# light_key_control.net
KiCad netlist of a schematic drawn in Altium Designer
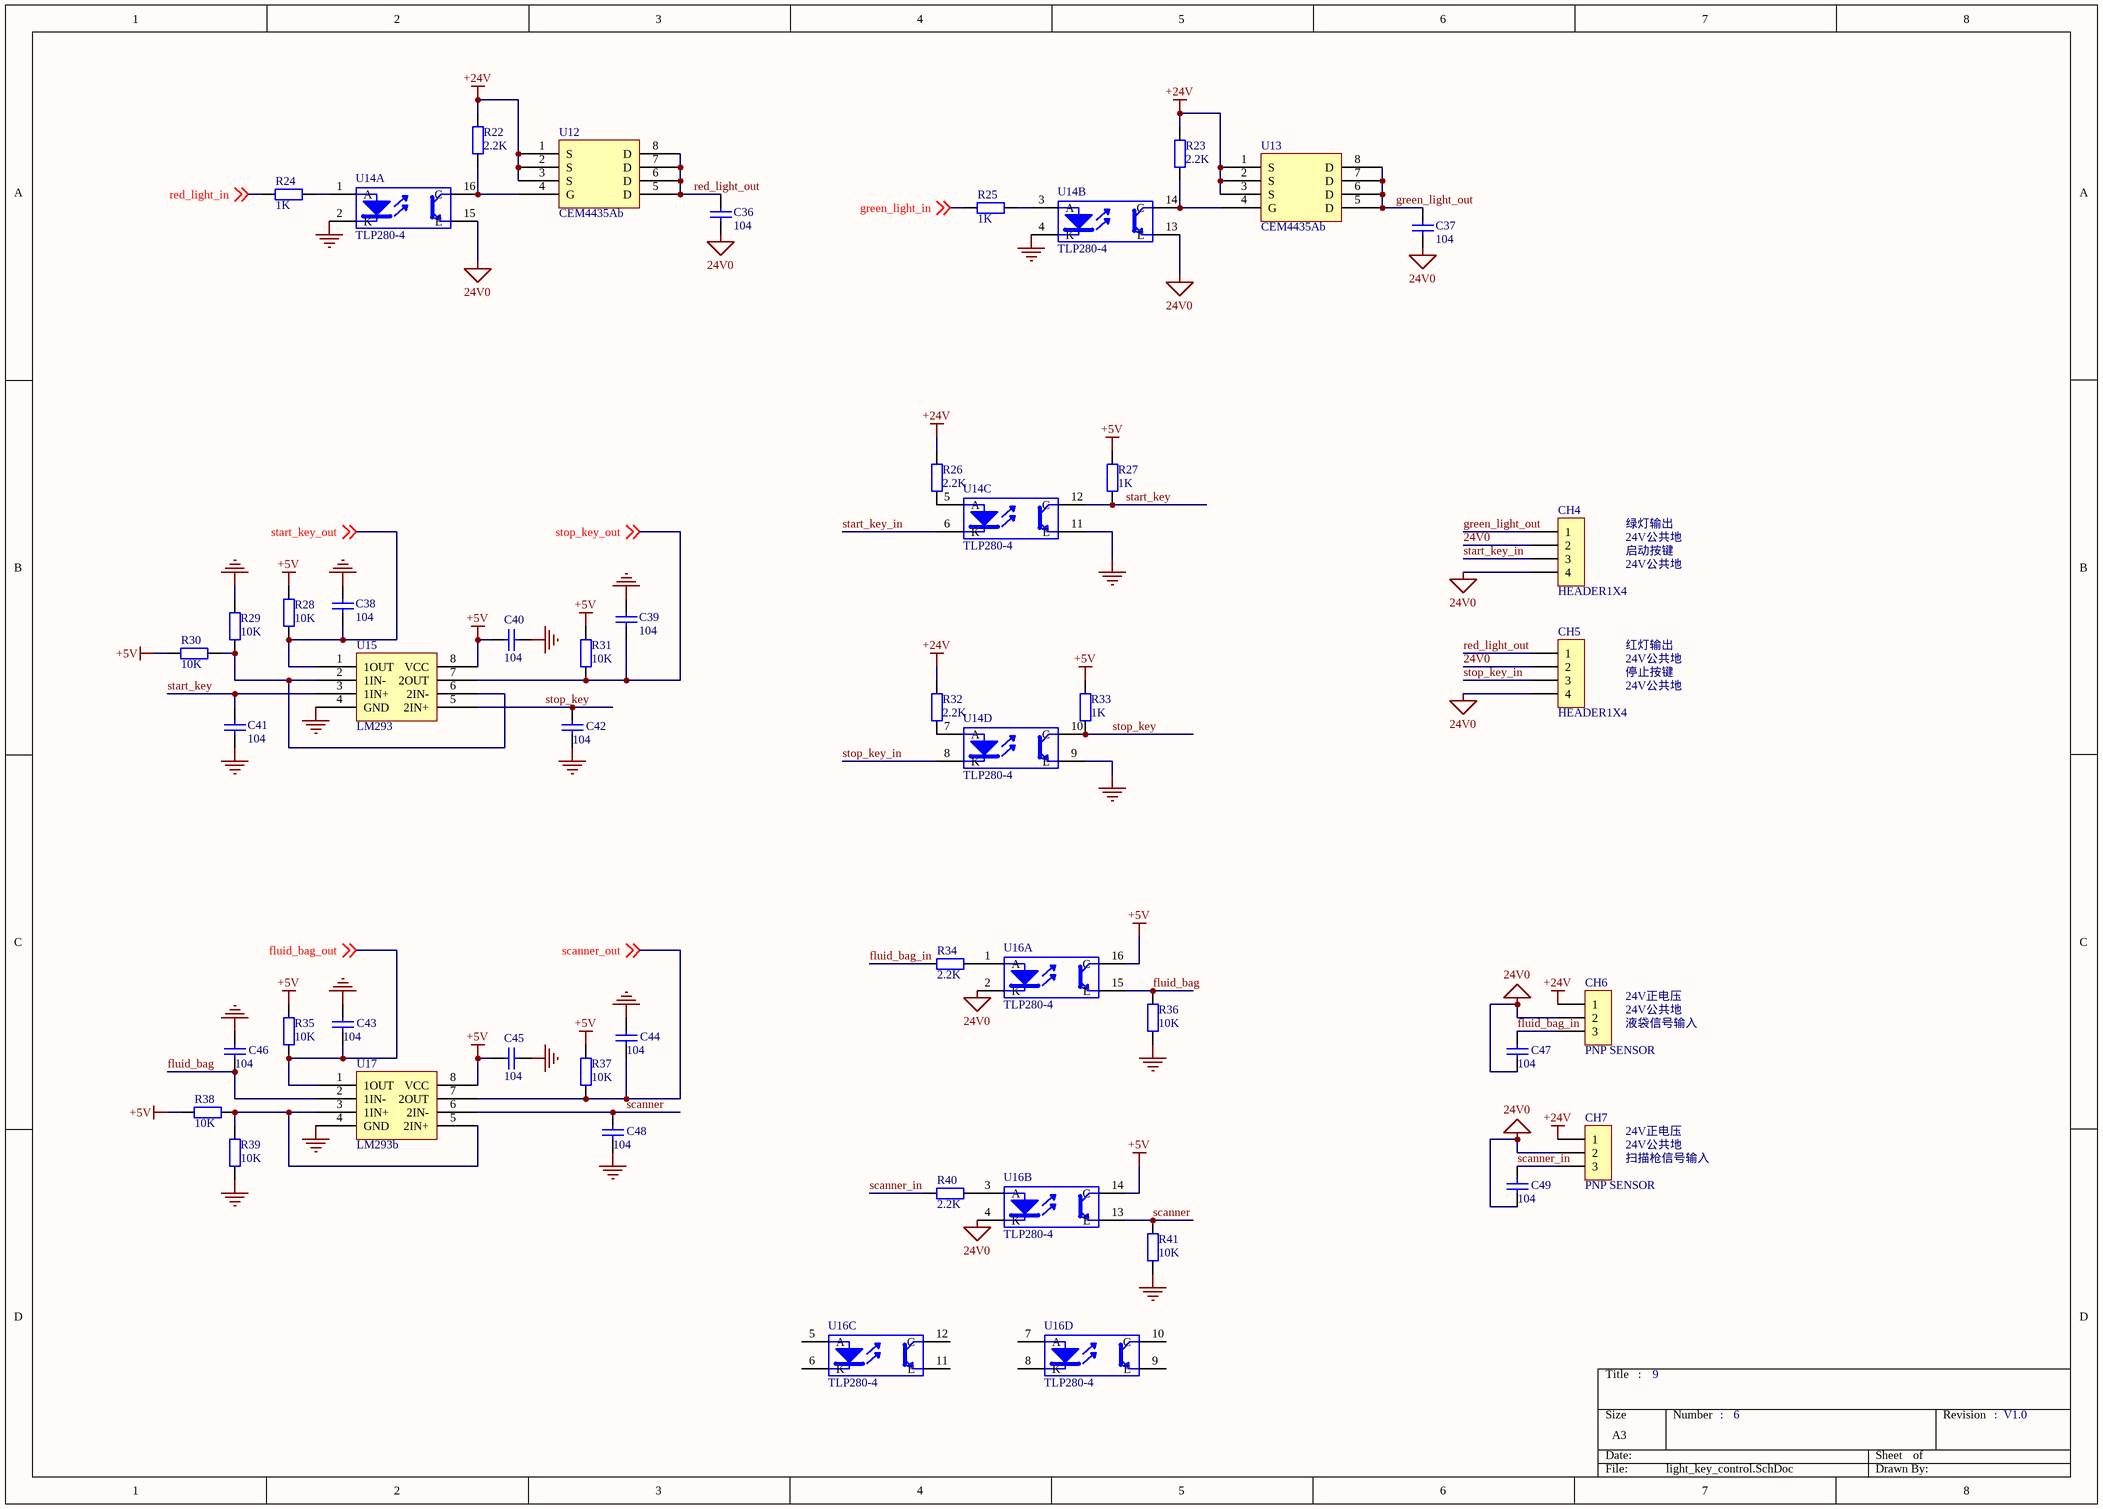
[diagram p0: light_key_control.SchDoc]

(export (version "E")
  (design (tool "Eeschema 10.0.6"))
  (components
    (comp (ref "C36")
      (value "104")
      (footprint "0805")
      (description "Capacitor")
      (fields (field (name "Comment") "Capb") (field (name "PUBLISHER") "Altium Limited"))
      (libsource (lib "Miscellaneous Devices") (part "Cap"))
    )
    (comp (ref "C37")
      (value "104")
      (footprint "0805")
      (description "Capacitor")
      (fields (field (name "Comment") "Capb") (field (name "PUBLISHER") "Altium Limited"))
      (libsource (lib "Miscellaneous Devices") (part "Cap"))
    )
    (comp (ref "C38")
      (value "104")
      (footprint "0805")
      (description "Capacitor")
      (fields (field (name "Comment") "Cap") (field (name "PUBLISHER") "Altium Limited"))
      (libsource (lib "Miscellaneous Devices") (part "Cap"))
    )
    (comp (ref "C39")
      (value "104")
      (footprint "0805")
      (description "Capacitor")
      (fields (field (name "Comment") "Cap") (field (name "PUBLISHER") "Altium Limited"))
      (libsource (lib "Miscellaneous Devices") (part "Cap"))
    )
    (comp (ref "C40")
      (value "104")
      (footprint "0805")
      (description "Capacitor")
      (fields (field (name "Comment") "Cap") (field (name "PUBLISHER") "Altium Limited"))
      (libsource (lib "Miscellaneous Devices") (part "Cap"))
    )
    (comp (ref "C41")
      (value "104")
      (footprint "0805")
      (description "Capacitor")
      (fields (field (name "Comment") "Cap") (field (name "PUBLISHER") "Altium Limited"))
      (libsource (lib "Miscellaneous Devices") (part "Cap"))
    )
    (comp (ref "C42")
      (value "104")
      (footprint "0805")
      (description "Capacitor")
      (fields (field (name "Comment") "Cap") (field (name "PUBLISHER") "Altium Limited"))
      (libsource (lib "Miscellaneous Devices") (part "Cap"))
    )
    (comp (ref "C43")
      (value "104")
      (footprint "0805")
      (description "Capacitor")
      (fields (field (name "Comment") "Capb") (field (name "PUBLISHER") "Altium Limited"))
      (libsource (lib "Miscellaneous Devices") (part "Cap"))
    )
    (comp (ref "C44")
      (value "104")
      (footprint "0805")
      (description "Capacitor")
      (fields (field (name "Comment") "Capb") (field (name "PUBLISHER") "Altium Limited"))
      (libsource (lib "Miscellaneous Devices") (part "Cap"))
    )
    (comp (ref "C45")
      (value "104")
      (footprint "0805")
      (description "Capacitor")
      (fields (field (name "Comment") "Cap") (field (name "PUBLISHER") "Altium Limited"))
      (libsource (lib "Miscellaneous Devices") (part "Cap"))
    )
    (comp (ref "C46")
      (value "104")
      (footprint "0805")
      (description "Capacitor")
      (fields (field (name "Comment") "Cap") (field (name "PUBLISHER") "Altium Limited"))
      (libsource (lib "Miscellaneous Devices") (part "Cap"))
    )
    (comp (ref "C47")
      (value "104")
      (footprint "0805")
      (description "Capacitor")
      (fields (field (name "Comment") "Capb") (field (name "PUBLISHER") "Altium Limited"))
      (libsource (lib "Miscellaneous Devices") (part "Cap"))
    )
    (comp (ref "C48")
      (value "104")
      (footprint "0805")
      (description "Capacitor")
      (fields (field (name "Comment") "Cap") (field (name "PUBLISHER") "Altium Limited"))
      (libsource (lib "Miscellaneous Devices") (part "Cap"))
    )
    (comp (ref "C49")
      (value "104")
      (footprint "0805")
      (description "Capacitor")
      (fields (field (name "Comment") "Capb") (field (name "PUBLISHER") "Altium Limited"))
      (libsource (lib "Miscellaneous Devices") (part "Cap"))
    )
    (comp (ref "CH4")
      (value "HEADER1X4")
      (footprint "CH3.96-4PIN")
      (libsource (lib "myIntegrated_Library1") (part "HEADER1X4"))
    )
    (comp (ref "CH5")
      (value "HEADER1X4")
      (footprint "CH3.96-4PIN")
      (libsource (lib "myIntegrated_Library1") (part "HEADER1X4"))
    )
    (comp (ref "CH6")
      (value "HEADER1X3")
      (footprint "CH3.96-3PIN")
      (fields (field (name "ALTIUM_UNNAMED_1") "PNP SENSOR"))
      (libsource (lib "myIntegrated_Library1") (part "HEADER1X3"))
    )
    (comp (ref "CH7")
      (value "HEADER1X3")
      (footprint "CH3.96-3PIN")
      (fields (field (name "ALTIUM_UNNAMED_1") "PNP SENSOR"))
      (libsource (lib "myIntegrated_Library1") (part "HEADER1X3"))
    )
    (comp (ref "R22")
      (value "2.2K")
      (footprint "0805")
      (description "Resistor")
      (fields (field (name "Comment") "Res2") (field (name "PUBLISHER") "Altium Limited"))
      (libsource (lib "") (part "Res2_3"))
    )
    (comp (ref "R23")
      (value "2.2K")
      (footprint "0805")
      (description "Resistor")
      (fields (field (name "Comment") "Res2") (field (name "PUBLISHER") "Altium Limited"))
      (libsource (lib "") (part "Res2_3"))
    )
    (comp (ref "R24")
      (value "1K")
      (footprint "0805")
      (description "Resistor")
      (fields (field (name "Comment") "Res2") (field (name "PUBLISHER") "Altium Limited"))
      (libsource (lib "Miscellaneous Devices") (part "Res2"))
    )
    (comp (ref "R25")
      (value "1K")
      (footprint "0805")
      (description "Resistor")
      (fields (field (name "Comment") "Res2") (field (name "PUBLISHER") "Altium Limited"))
      (libsource (lib "Miscellaneous Devices") (part "Res2"))
    )
    (comp (ref "R26")
      (value "2.2K")
      (footprint "0805")
      (description "Resistor")
      (fields (field (name "Comment") "Res2") (field (name "PUBLISHER") "Altium Limited"))
      (libsource (lib "") (part "Res2_1"))
    )
    (comp (ref "R27")
      (value "1K")
      (footprint "0805")
      (description "Resistor")
      (fields (field (name "Comment") "Res2") (field (name "PUBLISHER") "Altium Limited"))
      (libsource (lib "") (part "Res2_1"))
    )
    (comp (ref "R28")
      (value "10K")
      (footprint "0805")
      (description "Resistor")
      (fields (field (name "Comment") "Res2") (field (name "PUBLISHER") "Altium Limited"))
      (libsource (lib "") (part "Res2_1"))
    )
    (comp (ref "R29")
      (value "10K")
      (footprint "0805")
      (description "Resistor")
      (fields (field (name "Comment") "Res2") (field (name "PUBLISHER") "Altium Limited"))
      (libsource (lib "") (part "Res2_1"))
    )
    (comp (ref "R30")
      (value "10K")
      (footprint "0805")
      (description "Resistor")
      (fields (field (name "Comment") "Res2") (field (name "PUBLISHER") "Altium Limited"))
      (libsource (lib "") (part "Res2_2"))
    )
    (comp (ref "R31")
      (value "10K")
      (footprint "0805")
      (description "Resistor")
      (fields (field (name "Comment") "Res2") (field (name "PUBLISHER") "Altium Limited"))
      (libsource (lib "") (part "Res2_1"))
    )
    (comp (ref "R32")
      (value "2.2K")
      (footprint "0805")
      (description "Resistor")
      (fields (field (name "Comment") "Res2") (field (name "PUBLISHER") "Altium Limited"))
      (libsource (lib "") (part "Res2_1"))
    )
    (comp (ref "R33")
      (value "1K")
      (footprint "0805")
      (description "Resistor")
      (fields (field (name "Comment") "Res2") (field (name "PUBLISHER") "Altium Limited"))
      (libsource (lib "") (part "Res2_1"))
    )
    (comp (ref "R34")
      (value "2.2K")
      (footprint "0805")
      (description "Resistor")
      (fields (field (name "Comment") "Res2") (field (name "PUBLISHER") "Altium Limited"))
      (libsource (lib "") (part "Res2_2"))
    )
    (comp (ref "R35")
      (value "10K")
      (footprint "0805")
      (description "Resistor")
      (fields (field (name "Comment") "Res2b") (field (name "PUBLISHER") "Altium Limited"))
      (libsource (lib "") (part "Res2_1"))
    )
    (comp (ref "R36")
      (value "10K")
      (footprint "0805")
      (description "Resistor")
      (fields (field (name "Comment") "Res2") (field (name "PUBLISHER") "Altium Limited"))
      (libsource (lib "") (part "Res2_1"))
    )
    (comp (ref "R37")
      (value "10K")
      (footprint "0805")
      (description "Resistor")
      (fields (field (name "Comment") "Res2b") (field (name "PUBLISHER") "Altium Limited"))
      (libsource (lib "") (part "Res2_1"))
    )
    (comp (ref "R38")
      (value "10K")
      (footprint "0805")
      (description "Resistor")
      (fields (field (name "Comment") "Res2b") (field (name "PUBLISHER") "Altium Limited"))
      (libsource (lib "") (part "Res2_2"))
    )
    (comp (ref "R39")
      (value "10K")
      (footprint "0805")
      (description "Resistor")
      (fields (field (name "Comment") "Res2b") (field (name "PUBLISHER") "Altium Limited"))
      (libsource (lib "") (part "Res2_1"))
    )
    (comp (ref "R40")
      (value "2.2K")
      (footprint "0805")
      (description "Resistor")
      (fields (field (name "Comment") "Res2") (field (name "PUBLISHER") "Altium Limited"))
      (libsource (lib "") (part "Res2_2"))
    )
    (comp (ref "R41")
      (value "10K")
      (footprint "0805")
      (description "Resistor")
      (fields (field (name "Comment") "Res2") (field (name "PUBLISHER") "Altium Limited"))
      (libsource (lib "") (part "Res2_1"))
    )
    (comp (ref "U12")
      (value "CEM4435Ab")
      (footprint "SOP8-OP27")
      (libsource (lib "myIntegrated_Library1") (part "CEM4435A"))
    )
    (comp (ref "U13")
      (value "CEM4435Ab")
      (footprint "SOP8-OP27")
      (libsource (lib "myIntegrated_Library1") (part "CEM4435A"))
    )
    (comp (ref "U14") (value "TLP280-4") (footprint "SO16") (libsource (lib "WH V20") (part "TLP521-4")))
    (comp (ref "U15")
      (value "LM293")
      (footprint "SOP8-OP27")
      (libsource (lib "myIntegrated_Library1") (part "LM293"))
    )
    (comp (ref "U16") (value "TLP280-4") (footprint "SO16") (libsource (lib "WH V20") (part "TLP521-4")))
    (comp (ref "U17")
      (value "LM293b")
      (footprint "SOP8-OP27")
      (libsource (lib "myIntegrated_Library1") (part "LM293"))
    )
  )
  (nets
    (net (code "1") (name "+5V") (class "Default")
      (node (ref "C40") (pin "2") (pinfunction "2_2") (pintype "passive"))
      (node (ref "C45") (pin "2") (pinfunction "2_2") (pintype "passive"))
      (node (ref "R27") (pin "1") (pinfunction "1_1") (pintype "passive"))
      (node (ref "R28") (pin "1") (pinfunction "1_1") (pintype "passive"))
      (node (ref "R30") (pin "1") (pinfunction "1_1") (pintype "passive"))
      (node (ref "R31") (pin "1") (pinfunction "1_1") (pintype "passive"))
      (node (ref "R33") (pin "1") (pinfunction "1_1") (pintype "passive"))
      (node (ref "R35") (pin "1") (pinfunction "1_1") (pintype "passive"))
      (node (ref "R37") (pin "1") (pinfunction "1_1") (pintype "passive"))
      (node (ref "R38") (pin "1") (pinfunction "1_1") (pintype "passive"))
      (node (ref "U15") (pin "8") (pinfunction "VCC_8") (pintype "passive"))
      (node (ref "U16") (pin "14") (pinfunction "C_14") (pintype "passive"))
      (node (ref "U16") (pin "16") (pinfunction "C_16") (pintype "passive"))
      (node (ref "U17") (pin "8") (pinfunction "VCC_8") (pintype "passive"))
    )
    (net (code "2") (name "+24V") (class "Default")
      (node (ref "CH6") (pin "1") (pinfunction "1_1") (pintype "passive"))
      (node (ref "CH7") (pin "1") (pinfunction "1_1") (pintype "passive"))
      (node (ref "R22") (pin "2") (pinfunction "2_2") (pintype "passive"))
      (node (ref "R23") (pin "2") (pinfunction "2_2") (pintype "passive"))
      (node (ref "R26") (pin "1") (pinfunction "1_1") (pintype "passive"))
      (node (ref "R32") (pin "1") (pinfunction "1_1") (pintype "passive"))
      (node (ref "U12") (pin "1") (pinfunction "S_1") (pintype "passive"))
      (node (ref "U12") (pin "2") (pinfunction "S_2") (pintype "passive"))
      (node (ref "U12") (pin "3") (pinfunction "S_3") (pintype "passive"))
      (node (ref "U13") (pin "1") (pinfunction "S_1") (pintype "passive"))
      (node (ref "U13") (pin "2") (pinfunction "S_2") (pintype "passive"))
      (node (ref "U13") (pin "3") (pinfunction "S_3") (pintype "passive"))
    )
    (net (code "3") (name "/fluid_bag") (class "Default")
      (node (ref "C46") (pin "1") (pinfunction "1_1") (pintype "passive"))
      (node (ref "R36") (pin "1") (pinfunction "1_1") (pintype "passive"))
      (node (ref "U16") (pin "15") (pinfunction "E_15") (pintype "passive"))
      (node (ref "U17") (pin "2") (pinfunction "1IN-_2") (pintype "passive"))
    )
    (net (code "4") (name "/fluid_bag_in") (class "Default")
      (node (ref "C47") (pin "2") (pinfunction "2_2") (pintype "passive"))
      (node (ref "CH6") (pin "3") (pinfunction "3_3") (pintype "passive"))
      (node (ref "R34") (pin "1") (pinfunction "1_1") (pintype "passive"))
    )
    (net (code "5") (name "/green_light_out") (class "Default")
      (node (ref "C37") (pin "1") (pinfunction "1_1") (pintype "passive"))
      (node (ref "CH4") (pin "1") (pinfunction "1_1") (pintype "passive"))
      (node (ref "U13") (pin "5") (pinfunction "D_5") (pintype "passive"))
      (node (ref "U13") (pin "6") (pinfunction "D_6") (pintype "passive"))
      (node (ref "U13") (pin "7") (pinfunction "D_7") (pintype "passive"))
      (node (ref "U13") (pin "8") (pinfunction "D_8") (pintype "passive"))
    )
    (net (code "6") (name "/red_light_out") (class "Default")
      (node (ref "C36") (pin "1") (pinfunction "1_1") (pintype "passive"))
      (node (ref "CH5") (pin "1") (pinfunction "1_1") (pintype "passive"))
      (node (ref "U12") (pin "5") (pinfunction "D_5") (pintype "passive"))
      (node (ref "U12") (pin "6") (pinfunction "D_6") (pintype "passive"))
      (node (ref "U12") (pin "7") (pinfunction "D_7") (pintype "passive"))
      (node (ref "U12") (pin "8") (pinfunction "D_8") (pintype "passive"))
    )
    (net (code "7") (name "/scanner") (class "Default")
      (node (ref "C48") (pin "2") (pinfunction "2_2") (pintype "passive"))
      (node (ref "R41") (pin "1") (pinfunction "1_1") (pintype "passive"))
      (node (ref "U16") (pin "13") (pinfunction "E_13") (pintype "passive"))
      (node (ref "U17") (pin "6") (pinfunction "2IN-_6") (pintype "passive"))
    )
    (net (code "8") (name "/scanner_in") (class "Default")
      (node (ref "C49") (pin "2") (pinfunction "2_2") (pintype "passive"))
      (node (ref "CH7") (pin "3") (pinfunction "3_3") (pintype "passive"))
      (node (ref "R40") (pin "1") (pinfunction "1_1") (pintype "passive"))
    )
    (net (code "9") (name "/start_key") (class "Default")
      (node (ref "C41") (pin "2") (pinfunction "2_2") (pintype "passive"))
      (node (ref "R27") (pin "2") (pinfunction "2_2") (pintype "passive"))
      (node (ref "U14") (pin "12") (pinfunction "C_12") (pintype "passive"))
      (node (ref "U15") (pin "3") (pinfunction "1IN+_3") (pintype "passive"))
    )
    (net (code "10") (name "/start_key_in") (class "Default")
      (node (ref "CH4") (pin "3") (pinfunction "3_3") (pintype "passive"))
      (node (ref "U14") (pin "6") (pinfunction "K_6") (pintype "passive"))
    )
    (net (code "11") (name "/stop_key") (class "Default")
      (node (ref "C42") (pin "2") (pinfunction "2_2") (pintype "passive"))
      (node (ref "R33") (pin "2") (pinfunction "2_2") (pintype "passive"))
      (node (ref "U14") (pin "10") (pinfunction "C_10") (pintype "passive"))
      (node (ref "U15") (pin "5") (pinfunction "2IN+_5") (pintype "passive"))
    )
    (net (code "12") (name "/stop_key_in") (class "Default")
      (node (ref "CH5") (pin "3") (pinfunction "3_3") (pintype "passive"))
      (node (ref "U14") (pin "8") (pinfunction "K_8") (pintype "passive"))
    )
    (net (code "13") (name "24V0") (class "Default")
      (node (ref "C36") (pin "2") (pinfunction "2_2") (pintype "passive"))
      (node (ref "C37") (pin "2") (pinfunction "2_2") (pintype "passive"))
      (node (ref "C47") (pin "1") (pinfunction "1_1") (pintype "passive"))
      (node (ref "C49") (pin "1") (pinfunction "1_1") (pintype "passive"))
      (node (ref "CH4") (pin "2") (pinfunction "2_2") (pintype "passive"))
      (node (ref "CH4") (pin "4") (pinfunction "4_4") (pintype "passive"))
      (node (ref "CH5") (pin "2") (pinfunction "2_2") (pintype "passive"))
      (node (ref "CH5") (pin "4") (pinfunction "4_4") (pintype "passive"))
      (node (ref "CH6") (pin "2") (pinfunction "2_2") (pintype "passive"))
      (node (ref "CH7") (pin "2") (pinfunction "2_2") (pintype "passive"))
      (node (ref "U14") (pin "13") (pinfunction "E_13") (pintype "passive"))
      (node (ref "U14") (pin "15") (pinfunction "E_15") (pintype "passive"))
      (node (ref "U16") (pin "2") (pinfunction "K_2") (pintype "passive"))
      (node (ref "U16") (pin "4") (pinfunction "K_4") (pintype "passive"))
    )
    (net (code "14") (name "GND") (class "Default")
      (node (ref "C38") (pin "1") (pinfunction "1_1") (pintype "passive"))
      (node (ref "C39") (pin "1") (pinfunction "1_1") (pintype "passive"))
      (node (ref "C40") (pin "1") (pinfunction "1_1") (pintype "passive"))
      (node (ref "C41") (pin "1") (pinfunction "1_1") (pintype "passive"))
      (node (ref "C42") (pin "1") (pinfunction "1_1") (pintype "passive"))
      (node (ref "C43") (pin "2") (pinfunction "2_2") (pintype "passive"))
      (node (ref "C44") (pin "2") (pinfunction "2_2") (pintype "passive"))
      (node (ref "C45") (pin "1") (pinfunction "1_1") (pintype "passive"))
      (node (ref "C46") (pin "2") (pinfunction "2_2") (pintype "passive"))
      (node (ref "C48") (pin "1") (pinfunction "1_1") (pintype "passive"))
      (node (ref "R29") (pin "1") (pinfunction "1_1") (pintype "passive"))
      (node (ref "R36") (pin "2") (pinfunction "2_2") (pintype "passive"))
      (node (ref "R39") (pin "2") (pinfunction "2_2") (pintype "passive"))
      (node (ref "R41") (pin "2") (pinfunction "2_2") (pintype "passive"))
      (node (ref "U14") (pin "11") (pinfunction "E_11") (pintype "passive"))
      (node (ref "U14") (pin "2") (pinfunction "K_2") (pintype "passive"))
      (node (ref "U14") (pin "4") (pinfunction "K_4") (pintype "passive"))
      (node (ref "U14") (pin "9") (pinfunction "E_9") (pintype "passive"))
      (node (ref "U15") (pin "4") (pinfunction "GND_4") (pintype "passive"))
      (node (ref "U17") (pin "4") (pinfunction "GND_4") (pintype "passive"))
    )
    (net (code "15") (name "Net-(U12-G)") (class "Default")
      (node (ref "R22") (pin "1") (pinfunction "1_1") (pintype "passive"))
      (node (ref "U12") (pin "4") (pinfunction "G_4") (pintype "passive"))
      (node (ref "U14") (pin "16") (pinfunction "C_16") (pintype "passive"))
    )
    (net (code "16") (name "Net-(U13-G)") (class "Default")
      (node (ref "R23") (pin "1") (pinfunction "1_1") (pintype "passive"))
      (node (ref "U13") (pin "4") (pinfunction "G_4") (pintype "passive"))
      (node (ref "U14") (pin "14") (pinfunction "C_14") (pintype "passive"))
    )
    (net (code "17") (name "Net-(U14A-A)") (class "Default")
      (node (ref "R24") (pin "1") (pinfunction "1_1") (pintype "passive"))
      (node (ref "U14") (pin "1") (pinfunction "A_1") (pintype "passive"))
    )
    (net (code "18") (name "Net-(U14B-A)") (class "Default")
      (node (ref "R25") (pin "1") (pinfunction "1_1") (pintype "passive"))
      (node (ref "U14") (pin "3") (pinfunction "A_3") (pintype "passive"))
    )
    (net (code "19") (name "Net-(U14C-A)") (class "Default")
      (node (ref "R26") (pin "2") (pinfunction "2_2") (pintype "passive"))
      (node (ref "U14") (pin "5") (pinfunction "A_5") (pintype "passive"))
    )
    (net (code "20") (name "Net-(U14D-A)") (class "Default")
      (node (ref "R32") (pin "2") (pinfunction "2_2") (pintype "passive"))
      (node (ref "U14") (pin "7") (pinfunction "A_7") (pintype "passive"))
    )
    (net (code "21") (name "Net-(U15-1IN-)") (class "Default")
      (node (ref "R29") (pin "2") (pinfunction "2_2") (pintype "passive"))
      (node (ref "R30") (pin "2") (pinfunction "2_2") (pintype "passive"))
      (node (ref "U15") (pin "2") (pinfunction "1IN-_2") (pintype "passive"))
      (node (ref "U15") (pin "6") (pinfunction "2IN-_6") (pintype "passive"))
    )
    (net (code "22") (name "Net-(U16A-A)") (class "Default")
      (node (ref "R34") (pin "2") (pinfunction "2_2") (pintype "passive"))
      (node (ref "U16") (pin "1") (pinfunction "A_1") (pintype "passive"))
    )
    (net (code "23") (name "Net-(U16B-A)") (class "Default")
      (node (ref "R40") (pin "2") (pinfunction "2_2") (pintype "passive"))
      (node (ref "U16") (pin "3") (pinfunction "A_3") (pintype "passive"))
    )
    (net (code "24") (name "Net-(U17-1IN+)") (class "Default")
      (node (ref "R38") (pin "2") (pinfunction "2_2") (pintype "passive"))
      (node (ref "R39") (pin "1") (pinfunction "1_1") (pintype "passive"))
      (node (ref "U17") (pin "3") (pinfunction "1IN+_3") (pintype "passive"))
      (node (ref "U17") (pin "5") (pinfunction "2IN+_5") (pintype "passive"))
    )
    (net (code "25") (name "fluid_bag_out") (class "Default")
      (node (ref "C43") (pin "1") (pinfunction "1_1") (pintype "passive"))
      (node (ref "R35") (pin "2") (pinfunction "2_2") (pintype "passive"))
      (node (ref "U17") (pin "1") (pinfunction "1OUT_1") (pintype "passive"))
    )
    (net (code "26") (name "green_light_in") (class "Default")
      (node (ref "R25") (pin "2") (pinfunction "2_2") (pintype "passive"))
    )
    (net (code "27") (name "red_light_in") (class "Default")
      (node (ref "R24") (pin "2") (pinfunction "2_2") (pintype "passive"))
    )
    (net (code "28") (name "scanner_out") (class "Default")
      (node (ref "C44") (pin "1") (pinfunction "1_1") (pintype "passive"))
      (node (ref "R37") (pin "2") (pinfunction "2_2") (pintype "passive"))
      (node (ref "U17") (pin "7") (pinfunction "2OUT_7") (pintype "passive"))
    )
    (net (code "29") (name "start_key_out") (class "Default")
      (node (ref "C38") (pin "2") (pinfunction "2_2") (pintype "passive"))
      (node (ref "R28") (pin "2") (pinfunction "2_2") (pintype "passive"))
      (node (ref "U15") (pin "1") (pinfunction "1OUT_1") (pintype "passive"))
    )
    (net (code "30") (name "stop_key_out") (class "Default")
      (node (ref "C39") (pin "2") (pinfunction "2_2") (pintype "passive"))
      (node (ref "R31") (pin "2") (pinfunction "2_2") (pintype "passive"))
      (node (ref "U15") (pin "7") (pinfunction "2OUT_7") (pintype "passive"))
    )
    (net (code "31") (name "unconnected-(U16C-A-Pad5)") (class "Default")
      (node (ref "U16") (pin "5") (pinfunction "A_5") (pintype "passive"))
    )
    (net (code "32") (name "unconnected-(U16C-C-Pad12)") (class "Default")
      (node (ref "U16") (pin "12") (pinfunction "C_12") (pintype "passive"))
    )
    (net (code "33") (name "unconnected-(U16C-E-Pad11)") (class "Default")
      (node (ref "U16") (pin "11") (pinfunction "E_11") (pintype "passive"))
    )
    (net (code "34") (name "unconnected-(U16C-K-Pad6)") (class "Default")
      (node (ref "U16") (pin "6") (pinfunction "K_6") (pintype "passive"))
    )
    (net (code "35") (name "unconnected-(U16D-A-Pad7)") (class "Default")
      (node (ref "U16") (pin "7") (pinfunction "A_7") (pintype "passive"))
    )
    (net (code "36") (name "unconnected-(U16D-C-Pad10)") (class "Default")
      (node (ref "U16") (pin "10") (pinfunction "C_10") (pintype "passive"))
    )
    (net (code "37") (name "unconnected-(U16D-E-Pad9)") (class "Default")
      (node (ref "U16") (pin "9") (pinfunction "E_9") (pintype "passive"))
    )
    (net (code "38") (name "unconnected-(U16D-K-Pad8)") (class "Default")
      (node (ref "U16") (pin "8") (pinfunction "K_8") (pintype "passive"))
    )
  )
)
